# ADCduinoModule_Sensor_1.net
KiCad netlist of a schematic drawn in Altium Designer
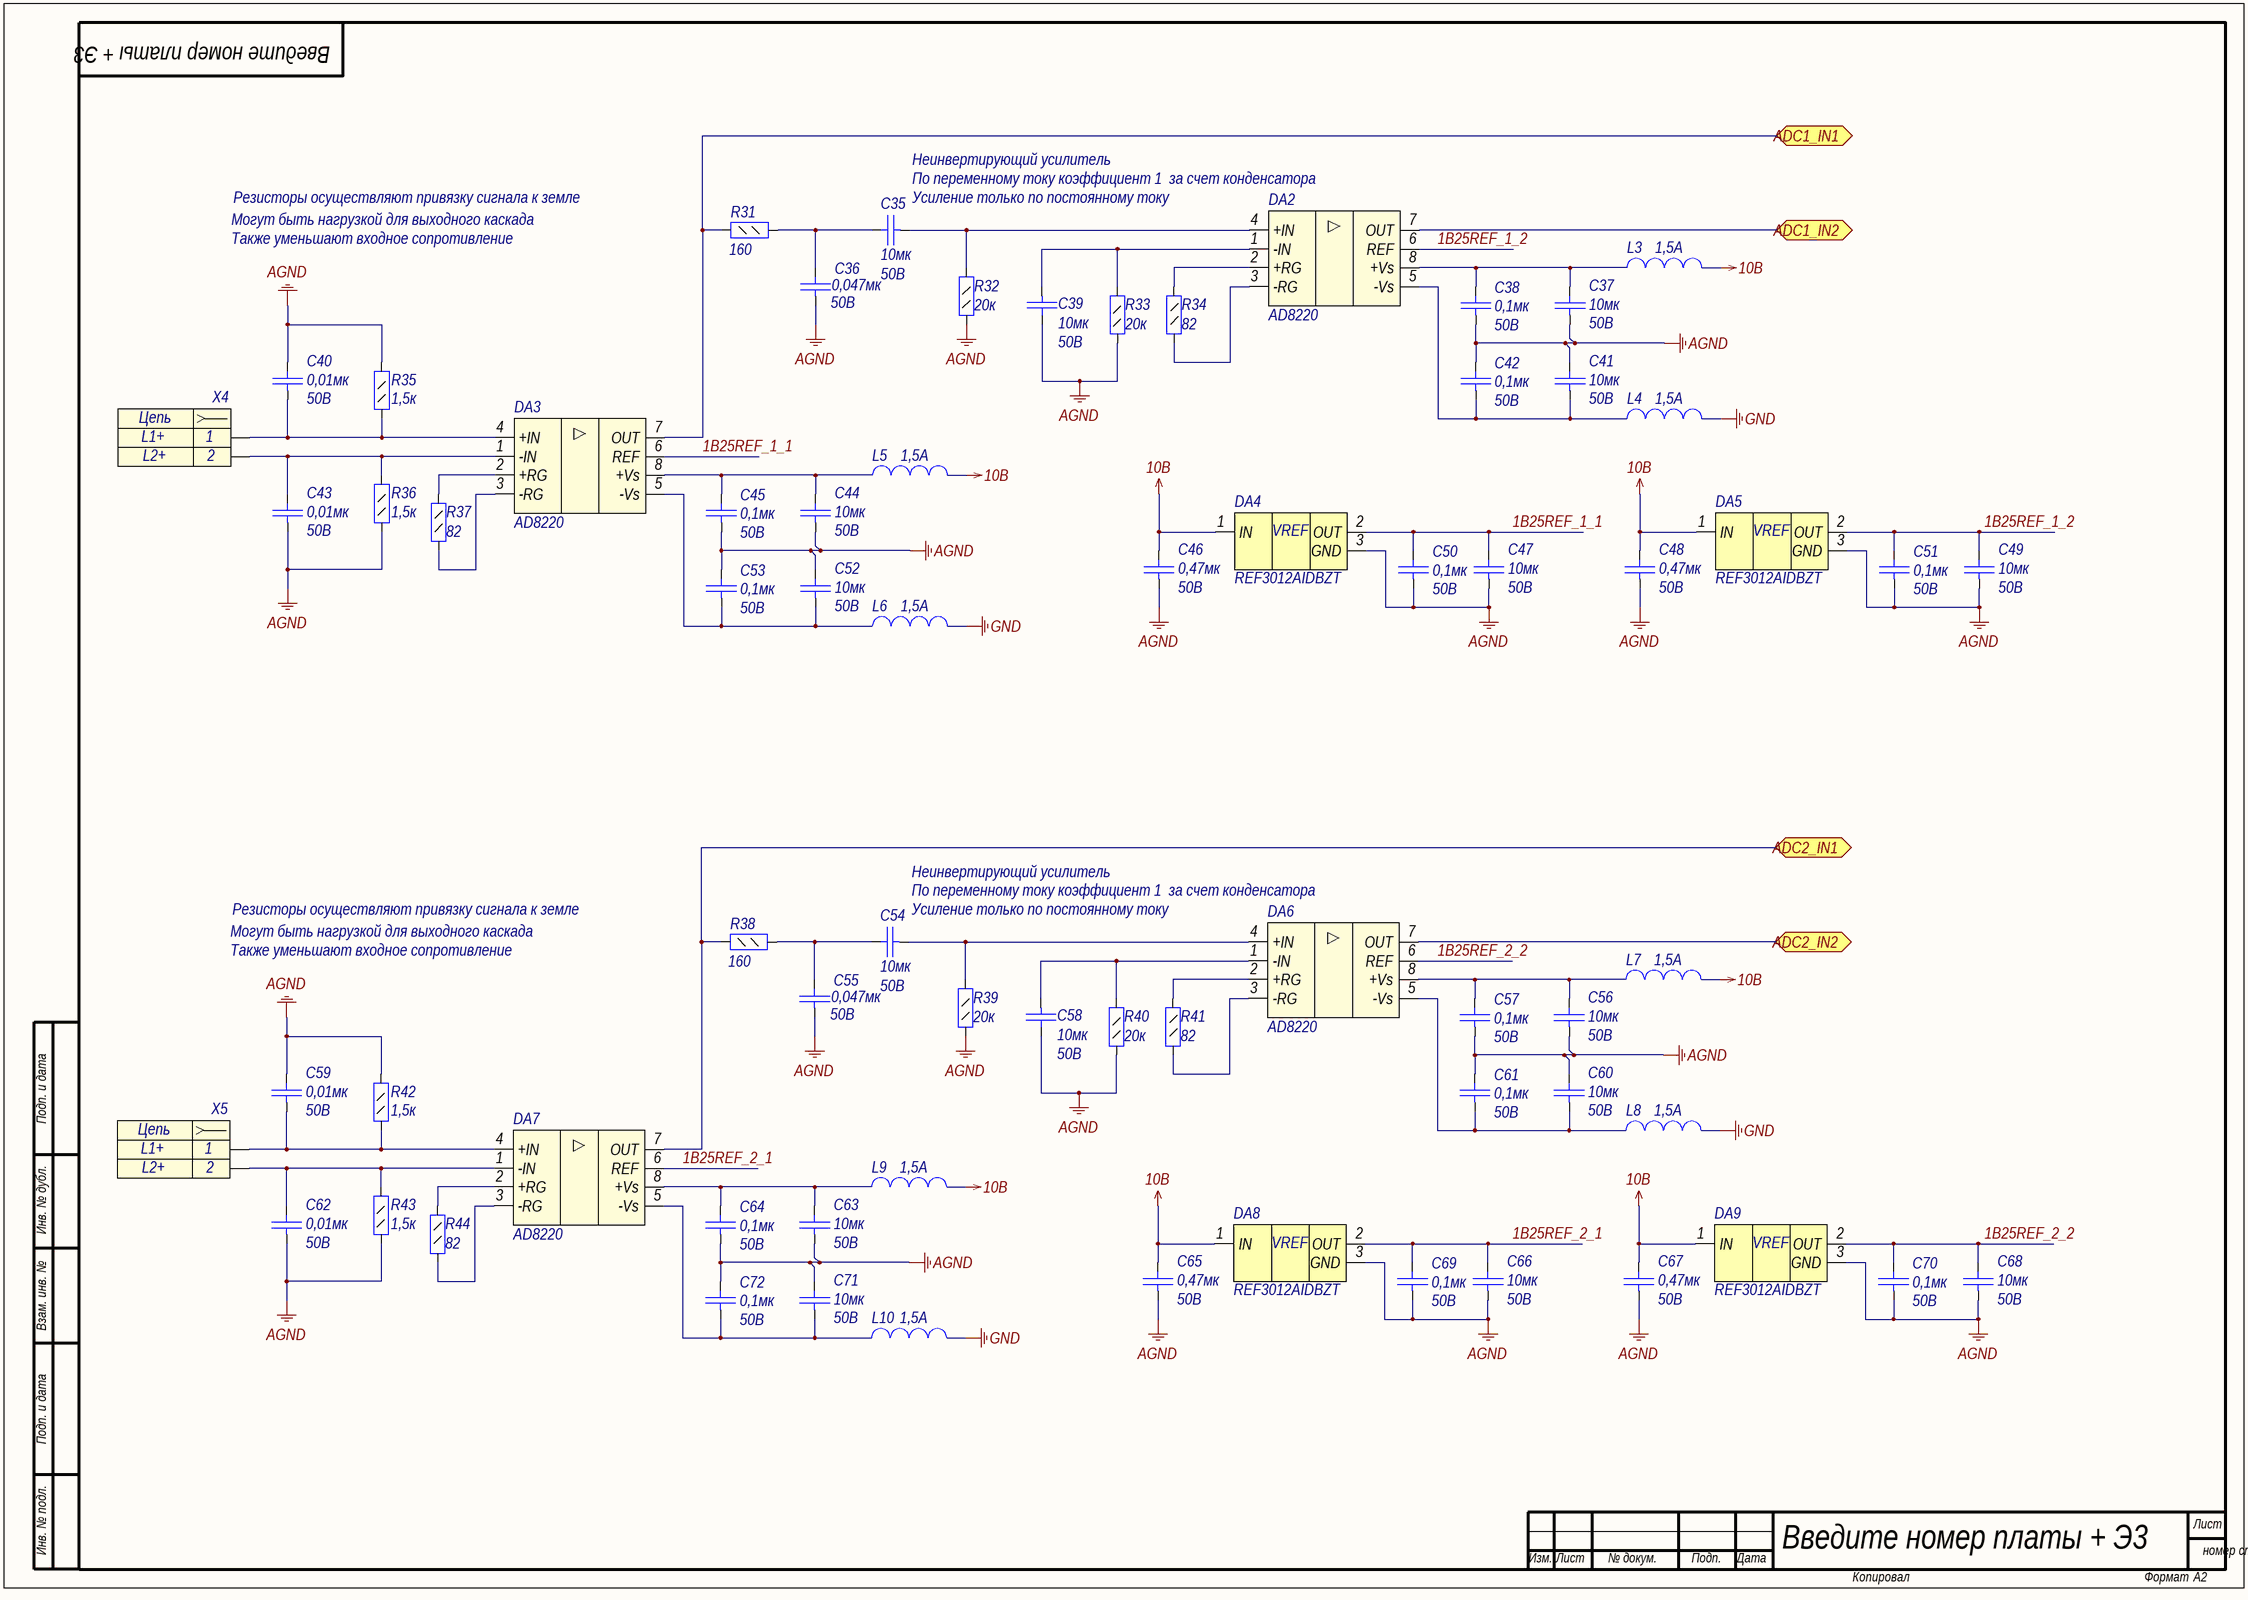
[diagram p0: ADCduinoModule_Sensor_1.SchDoc]

(export (version "E")
  (design (tool "Eeschema 10.0.6"))
  (components
    (comp (ref "C35")
      (value "10мк")
      (footprint "C1210")
      (description "Конденсатор")
      (fields
        (field (name "VOLTAGE") "50В")
        (field (name "PART NUMBER") "GRM32ER71H106K")
        (field (name "Comment") "Capacitor")
      )
      (libsource (lib "MOP44") (part "Capacitor"))
    )
    (comp (ref "C36")
      (value "0,047мк")
      (footprint "C0805")
      (description "Конденсатор")
      (fields
        (field (name "VOLTAGE") "50B")
        (field (name "PART NUMBER") "GRM21BR71H473K")
        (field (name "Comment") "Capacitor")
      )
      (libsource (lib "MOP44") (part "Capacitor"))
    )
    (comp (ref "C37")
      (value "10мк")
      (footprint "C1210")
      (description "Конденсатор")
      (fields
        (field (name "VOLTAGE") "50В")
        (field (name "PART NUMBER") "GRM32ER71H106K")
        (field (name "Comment") "Capacitor")
      )
      (libsource (lib "MOP44") (part "Capacitor"))
    )
    (comp (ref "C38")
      (value "0,1мк")
      (footprint "C0805")
      (description "Конденсатор")
      (fields
        (field (name "VOLTAGE") "50B")
        (field (name "PART NUMBER") "GRM21BR71H104K**")
        (field (name "Comment") "Capacitor")
      )
      (libsource (lib "MOP44") (part "Capacitor"))
    )
    (comp (ref "C39")
      (value "10мк")
      (footprint "C1210")
      (description "Конденсатор")
      (fields
        (field (name "VOLTAGE") "50В")
        (field (name "PART NUMBER") "GRM32ER71H106K")
        (field (name "Comment") "Capacitor")
      )
      (libsource (lib "MOP44") (part "Capacitor"))
    )
    (comp (ref "C40")
      (value "0,01мк")
      (footprint "C0805")
      (description "Конденсатор")
      (fields
        (field (name "VOLTAGE") "50B")
        (field (name "PART NUMBER") "GRM216R71H103K")
        (field (name "Comment") "Capacitor")
      )
      (libsource (lib "MOP44") (part "Capacitor"))
    )
    (comp (ref "C41")
      (value "10мк")
      (footprint "C1210")
      (description "Конденсатор")
      (fields
        (field (name "VOLTAGE") "50В")
        (field (name "PART NUMBER") "GRM32ER71H106K")
        (field (name "Comment") "Capacitor")
      )
      (libsource (lib "MOP44") (part "Capacitor"))
    )
    (comp (ref "C42")
      (value "0,1мк")
      (footprint "C0805")
      (description "Конденсатор")
      (fields
        (field (name "VOLTAGE") "50B")
        (field (name "PART NUMBER") "GRM21BR71H104K**")
        (field (name "Comment") "Capacitor")
      )
      (libsource (lib "MOP44") (part "Capacitor"))
    )
    (comp (ref "C43")
      (value "0,01мк")
      (footprint "C0805")
      (description "Конденсатор")
      (fields
        (field (name "VOLTAGE") "50B")
        (field (name "PART NUMBER") "GRM216R71H103K")
        (field (name "Comment") "Capacitor")
      )
      (libsource (lib "MOP44") (part "Capacitor"))
    )
    (comp (ref "C44")
      (value "10мк")
      (footprint "C1210")
      (description "Конденсатор")
      (fields
        (field (name "VOLTAGE") "50В")
        (field (name "PART NUMBER") "GRM32ER71H106K")
        (field (name "Comment") "Capacitor")
      )
      (libsource (lib "MOP44") (part "Capacitor"))
    )
    (comp (ref "C45")
      (value "0,1мк")
      (footprint "C0805")
      (description "Конденсатор")
      (fields
        (field (name "VOLTAGE") "50B")
        (field (name "PART NUMBER") "GRM21BR71H104K**")
        (field (name "Comment") "Capacitor")
      )
      (libsource (lib "MOP44") (part "Capacitor"))
    )
    (comp (ref "C46")
      (value "0,47мк")
      (footprint "C0805")
      (description "Конденсатор")
      (fields
        (field (name "VOLTAGE") "50B")
        (field (name "PART NUMBER") "GRM219R71C474K")
        (field (name "Comment") "Capacitor")
      )
      (libsource (lib "MOP44") (part "Capacitor"))
    )
    (comp (ref "C47")
      (value "10мк")
      (footprint "C1210")
      (description "Конденсатор")
      (fields
        (field (name "VOLTAGE") "50В")
        (field (name "PART NUMBER") "GRM32ER71H106K")
        (field (name "Comment") "Capacitor")
      )
      (libsource (lib "MOP44") (part "Capacitor"))
    )
    (comp (ref "C48")
      (value "0,47мк")
      (footprint "C0805")
      (description "Конденсатор")
      (fields
        (field (name "VOLTAGE") "50B")
        (field (name "PART NUMBER") "GRM219R71C474K")
        (field (name "Comment") "Capacitor")
      )
      (libsource (lib "MOP44") (part "Capacitor"))
    )
    (comp (ref "C49")
      (value "10мк")
      (footprint "C1210")
      (description "Конденсатор")
      (fields
        (field (name "VOLTAGE") "50В")
        (field (name "PART NUMBER") "GRM32ER71H106K")
        (field (name "Comment") "Capacitor")
      )
      (libsource (lib "MOP44") (part "Capacitor"))
    )
    (comp (ref "C50")
      (value "0,1мк")
      (footprint "C0805")
      (description "Конденсатор")
      (fields
        (field (name "VOLTAGE") "50B")
        (field (name "PART NUMBER") "GRM21BR71H104K**")
        (field (name "Comment") "Capacitor")
      )
      (libsource (lib "MOP44") (part "Capacitor"))
    )
    (comp (ref "C51")
      (value "0,1мк")
      (footprint "C0805")
      (description "Конденсатор")
      (fields
        (field (name "VOLTAGE") "50B")
        (field (name "PART NUMBER") "GRM21BR71H104K**")
        (field (name "Comment") "Capacitor")
      )
      (libsource (lib "MOP44") (part "Capacitor"))
    )
    (comp (ref "C52")
      (value "10мк")
      (footprint "C1210")
      (description "Конденсатор")
      (fields
        (field (name "VOLTAGE") "50В")
        (field (name "PART NUMBER") "GRM32ER71H106K")
        (field (name "Comment") "Capacitor")
      )
      (libsource (lib "MOP44") (part "Capacitor"))
    )
    (comp (ref "C53")
      (value "0,1мк")
      (footprint "C0805")
      (description "Конденсатор")
      (fields
        (field (name "VOLTAGE") "50B")
        (field (name "PART NUMBER") "GRM21BR71H104K**")
        (field (name "Comment") "Capacitor")
      )
      (libsource (lib "MOP44") (part "Capacitor"))
    )
    (comp (ref "C54")
      (value "10мк")
      (footprint "C1210")
      (description "Конденсатор")
      (fields
        (field (name "VOLTAGE") "50В")
        (field (name "PART NUMBER") "GRM32ER71H106K")
        (field (name "Comment") "Capacitor")
      )
      (libsource (lib "MOP44") (part "Capacitor"))
    )
    (comp (ref "C55")
      (value "0,047мк")
      (footprint "C0805")
      (description "Конденсатор")
      (fields
        (field (name "VOLTAGE") "50B")
        (field (name "PART NUMBER") "GRM21BR71H473K")
        (field (name "Comment") "Capacitor")
      )
      (libsource (lib "MOP44") (part "Capacitor"))
    )
    (comp (ref "C56")
      (value "10мк")
      (footprint "C1210")
      (description "Конденсатор")
      (fields
        (field (name "VOLTAGE") "50В")
        (field (name "PART NUMBER") "GRM32ER71H106K")
        (field (name "Comment") "Capacitor")
      )
      (libsource (lib "MOP44") (part "Capacitor"))
    )
    (comp (ref "C57")
      (value "0,1мк")
      (footprint "C0805")
      (description "Конденсатор")
      (fields
        (field (name "VOLTAGE") "50B")
        (field (name "PART NUMBER") "GRM21BR71H104K**")
        (field (name "Comment") "Capacitor")
      )
      (libsource (lib "MOP44") (part "Capacitor"))
    )
    (comp (ref "C58")
      (value "10мк")
      (footprint "C1210")
      (description "Конденсатор")
      (fields
        (field (name "VOLTAGE") "50В")
        (field (name "PART NUMBER") "GRM32ER71H106K")
        (field (name "Comment") "Capacitor")
      )
      (libsource (lib "MOP44") (part "Capacitor"))
    )
    (comp (ref "C59")
      (value "0,01мк")
      (footprint "C0805")
      (description "Конденсатор")
      (fields
        (field (name "VOLTAGE") "50B")
        (field (name "PART NUMBER") "GRM216R71H103K")
        (field (name "Comment") "Capacitor")
      )
      (libsource (lib "MOP44") (part "Capacitor"))
    )
    (comp (ref "C60")
      (value "10мк")
      (footprint "C1210")
      (description "Конденсатор")
      (fields
        (field (name "VOLTAGE") "50В")
        (field (name "PART NUMBER") "GRM32ER71H106K")
        (field (name "Comment") "Capacitor")
      )
      (libsource (lib "MOP44") (part "Capacitor"))
    )
    (comp (ref "C61")
      (value "0,1мк")
      (footprint "C0805")
      (description "Конденсатор")
      (fields
        (field (name "VOLTAGE") "50B")
        (field (name "PART NUMBER") "GRM21BR71H104K**")
        (field (name "Comment") "Capacitor")
      )
      (libsource (lib "MOP44") (part "Capacitor"))
    )
    (comp (ref "C62")
      (value "0,01мк")
      (footprint "C0805")
      (description "Конденсатор")
      (fields
        (field (name "VOLTAGE") "50B")
        (field (name "PART NUMBER") "GRM216R71H103K")
        (field (name "Comment") "Capacitor")
      )
      (libsource (lib "MOP44") (part "Capacitor"))
    )
    (comp (ref "C63")
      (value "10мк")
      (footprint "C1210")
      (description "Конденсатор")
      (fields
        (field (name "VOLTAGE") "50В")
        (field (name "PART NUMBER") "GRM32ER71H106K")
        (field (name "Comment") "Capacitor")
      )
      (libsource (lib "MOP44") (part "Capacitor"))
    )
    (comp (ref "C64")
      (value "0,1мк")
      (footprint "C0805")
      (description "Конденсатор")
      (fields
        (field (name "VOLTAGE") "50B")
        (field (name "PART NUMBER") "GRM21BR71H104K**")
        (field (name "Comment") "Capacitor")
      )
      (libsource (lib "MOP44") (part "Capacitor"))
    )
    (comp (ref "C65")
      (value "0,47мк")
      (footprint "C0805")
      (description "Конденсатор")
      (fields
        (field (name "VOLTAGE") "50B")
        (field (name "PART NUMBER") "GRM219R71C474K")
        (field (name "Comment") "Capacitor")
      )
      (libsource (lib "MOP44") (part "Capacitor"))
    )
    (comp (ref "C66")
      (value "10мк")
      (footprint "C1210")
      (description "Конденсатор")
      (fields
        (field (name "VOLTAGE") "50В")
        (field (name "PART NUMBER") "GRM32ER71H106K")
        (field (name "Comment") "Capacitor")
      )
      (libsource (lib "MOP44") (part "Capacitor"))
    )
    (comp (ref "C67")
      (value "0,47мк")
      (footprint "C0805")
      (description "Конденсатор")
      (fields
        (field (name "VOLTAGE") "50B")
        (field (name "PART NUMBER") "GRM219R71C474K")
        (field (name "Comment") "Capacitor")
      )
      (libsource (lib "MOP44") (part "Capacitor"))
    )
    (comp (ref "C68")
      (value "10мк")
      (footprint "C1210")
      (description "Конденсатор")
      (fields
        (field (name "VOLTAGE") "50В")
        (field (name "PART NUMBER") "GRM32ER71H106K")
        (field (name "Comment") "Capacitor")
      )
      (libsource (lib "MOP44") (part "Capacitor"))
    )
    (comp (ref "C69")
      (value "0,1мк")
      (footprint "C0805")
      (description "Конденсатор")
      (fields
        (field (name "VOLTAGE") "50B")
        (field (name "PART NUMBER") "GRM21BR71H104K**")
        (field (name "Comment") "Capacitor")
      )
      (libsource (lib "MOP44") (part "Capacitor"))
    )
    (comp (ref "C70")
      (value "0,1мк")
      (footprint "C0805")
      (description "Конденсатор")
      (fields
        (field (name "VOLTAGE") "50B")
        (field (name "PART NUMBER") "GRM21BR71H104K**")
        (field (name "Comment") "Capacitor")
      )
      (libsource (lib "MOP44") (part "Capacitor"))
    )
    (comp (ref "C71")
      (value "10мк")
      (footprint "C1210")
      (description "Конденсатор")
      (fields
        (field (name "VOLTAGE") "50В")
        (field (name "PART NUMBER") "GRM32ER71H106K")
        (field (name "Comment") "Capacitor")
      )
      (libsource (lib "MOP44") (part "Capacitor"))
    )
    (comp (ref "C72")
      (value "0,1мк")
      (footprint "C0805")
      (description "Конденсатор")
      (fields
        (field (name "VOLTAGE") "50B")
        (field (name "PART NUMBER") "GRM21BR71H104K**")
        (field (name "Comment") "Capacitor")
      )
      (libsource (lib "MOP44") (part "Capacitor"))
    )
    (comp (ref "DA2")
      (value "AD8220")
      (footprint "MSOP8")
      (description "JFET Input Instrumentation Amplifier")
      (fields (field (name "PART NUMBER") "AD8220ARMZ"))
      (libsource (lib "MOP44") (part "AD8220"))
    )
    (comp (ref "DA3")
      (value "AD8220")
      (footprint "MSOP8")
      (description "JFET Input Instrumentation Amplifier")
      (fields (field (name "PART NUMBER") "AD8220ARMZ"))
      (libsource (lib "MOP44") (part "AD8220"))
    )
    (comp (ref "DA4")
      (value "REF30xx")
      (footprint "SOT23-3")
      (description "CMOS Voltage Reference")
      (fields (field (name "PART NUMBER") "REF3012AIDBZT") (field (name "MANUFACTURER") "Texas Instruments"))
      (libsource (lib "MOP44") (part "REF30xx"))
    )
    (comp (ref "DA5")
      (value "REF30xx")
      (footprint "SOT23-3")
      (description "CMOS Voltage Reference")
      (fields (field (name "PART NUMBER") "REF3012AIDBZT") (field (name "MANUFACTURER") "Texas Instruments"))
      (libsource (lib "MOP44") (part "REF30xx"))
    )
    (comp (ref "DA6")
      (value "AD8220")
      (footprint "MSOP8")
      (description "JFET Input Instrumentation Amplifier")
      (fields (field (name "PART NUMBER") "AD8220ARMZ"))
      (libsource (lib "") (part "AD8220_1"))
    )
    (comp (ref "DA7")
      (value "AD8220")
      (footprint "MSOP8")
      (description "JFET Input Instrumentation Amplifier")
      (fields (field (name "PART NUMBER") "AD8220ARMZ"))
      (libsource (lib "") (part "AD8220_1"))
    )
    (comp (ref "DA8")
      (value "REF30xx")
      (footprint "SOT23-3")
      (description "CMOS Voltage Reference")
      (fields (field (name "PART NUMBER") "REF3012AIDBZT") (field (name "MANUFACTURER") "Texas Instruments"))
      (libsource (lib "MOP44") (part "REF30xx"))
    )
    (comp (ref "DA9")
      (value "REF30xx")
      (footprint "SOT23-3")
      (description "CMOS Voltage Reference")
      (fields (field (name "PART NUMBER") "REF3012AIDBZT") (field (name "MANUFACTURER") "Texas Instruments"))
      (libsource (lib "MOP44") (part "REF30xx"))
    )
    (comp (ref "L3")
      (value "Inductor")
      (footprint "L0603")
      (description "EMI Suppression Filter")
      (fields (field (name "RATED CURRENT") "1,5A") (field (name "PART NUMBER") "BLM18PG181SN1D"))
      (libsource (lib "MOP44") (part "Inductor"))
    )
    (comp (ref "L4")
      (value "Inductor")
      (footprint "L0603")
      (description "EMI Suppression Filter")
      (fields (field (name "RATED CURRENT") "1,5A") (field (name "PART NUMBER") "BLM18PG181SN1D"))
      (libsource (lib "MOP44") (part "Inductor"))
    )
    (comp (ref "L5")
      (value "Inductor")
      (footprint "L0603")
      (description "EMI Suppression Filter")
      (fields (field (name "RATED CURRENT") "1,5A") (field (name "PART NUMBER") "BLM18PG181SN1D"))
      (libsource (lib "MOP44") (part "Inductor"))
    )
    (comp (ref "L6")
      (value "Inductor")
      (footprint "L0603")
      (description "EMI Suppression Filter")
      (fields (field (name "RATED CURRENT") "1,5A") (field (name "PART NUMBER") "BLM18PG181SN1D"))
      (libsource (lib "MOP44") (part "Inductor"))
    )
    (comp (ref "L7")
      (value "Inductor")
      (footprint "L0603")
      (description "EMI Suppression Filter")
      (fields (field (name "RATED CURRENT") "1,5A") (field (name "PART NUMBER") "BLM18PG181SN1D"))
      (libsource (lib "MOP44") (part "Inductor"))
    )
    (comp (ref "L8")
      (value "Inductor")
      (footprint "L0603")
      (description "EMI Suppression Filter")
      (fields (field (name "RATED CURRENT") "1,5A") (field (name "PART NUMBER") "BLM18PG181SN1D"))
      (libsource (lib "MOP44") (part "Inductor"))
    )
    (comp (ref "L9")
      (value "Inductor")
      (footprint "L0603")
      (description "EMI Suppression Filter")
      (fields (field (name "RATED CURRENT") "1,5A") (field (name "PART NUMBER") "BLM18PG181SN1D"))
      (libsource (lib "MOP44") (part "Inductor"))
    )
    (comp (ref "L10")
      (value "Inductor")
      (footprint "L0603")
      (description "EMI Suppression Filter")
      (fields (field (name "RATED CURRENT") "1,5A") (field (name "PART NUMBER") "BLM18PG181SN1D"))
      (libsource (lib "MOP44") (part "Inductor"))
    )
    (comp (ref "R31")
      (value "160")
      (footprint "R0805")
      (description "Резистор")
      (fields (field (name "PART NUMBER") "RC0805FR-07160RL") (field (name "POWER") "0,125Вт"))
      (libsource (lib "") (part "Resistor_0,125Вт_2"))
    )
    (comp (ref "R32")
      (value "20к")
      (footprint "R0805")
      (description "Резистор")
      (fields (field (name "PART NUMBER") "RC0805FR-0720KL") (field (name "POWER") "0,125Вт"))
      (libsource (lib "") (part "Resistor_0,125Вт_1"))
    )
    (comp (ref "R33")
      (value "20к")
      (footprint "R0805")
      (description "Резистор")
      (fields (field (name "PART NUMBER") "RC0805FR-0720KL") (field (name "POWER") "0,125Вт"))
      (libsource (lib "") (part "Resistor_0,125Вт_1"))
    )
    (comp (ref "R34")
      (value "82")
      (footprint "R0805")
      (description "Резистор")
      (fields (field (name "PART NUMBER") "RC0805FR-0782RL") (field (name "POWER") "0,125Вт"))
      (libsource (lib "MOP44") (part "Resistor_0,125Вт"))
    )
    (comp (ref "R35")
      (value "1,5к")
      (footprint "R0805")
      (description "Резистор")
      (fields (field (name "PART NUMBER") "RC0805FR-071K5") (field (name "POWER") "0,125Вт"))
      (libsource (lib "") (part "Resistor_0,125Вт_1"))
    )
    (comp (ref "R36")
      (value "1,5к")
      (footprint "R0805")
      (description "Резистор")
      (fields (field (name "PART NUMBER") "RC0805FR-071K5") (field (name "POWER") "0,125Вт"))
      (libsource (lib "") (part "Resistor_0,125Вт_1"))
    )
    (comp (ref "R37")
      (value "82")
      (footprint "R0805")
      (description "Резистор")
      (fields (field (name "PART NUMBER") "RC0805FR-0782RL") (field (name "POWER") "0,125Вт"))
      (libsource (lib "MOP44") (part "Resistor_0,125Вт"))
    )
    (comp (ref "R38")
      (value "160")
      (footprint "R0805")
      (description "Резистор")
      (fields (field (name "PART NUMBER") "RC0805FR-07160RL") (field (name "POWER") "0,125Вт"))
      (libsource (lib "") (part "Resistor_0,125Вт_2"))
    )
    (comp (ref "R39")
      (value "20к")
      (footprint "R0805")
      (description "Резистор")
      (fields (field (name "PART NUMBER") "RC0805FR-0720KL") (field (name "POWER") "0,125Вт"))
      (libsource (lib "") (part "Resistor_0,125Вт_1"))
    )
    (comp (ref "R40")
      (value "20к")
      (footprint "R0805")
      (description "Резистор")
      (fields (field (name "PART NUMBER") "RC0805FR-0720KL") (field (name "POWER") "0,125Вт"))
      (libsource (lib "") (part "Resistor_0,125Вт_1"))
    )
    (comp (ref "R41")
      (value "82")
      (footprint "R0805")
      (description "Резистор")
      (fields (field (name "PART NUMBER") "RC0805FR-0782RL") (field (name "POWER") "0,125Вт"))
      (libsource (lib "MOP44") (part "Resistor_0,125Вт"))
    )
    (comp (ref "R42")
      (value "1,5к")
      (footprint "R0805")
      (description "Резистор")
      (fields (field (name "PART NUMBER") "RC0805FR-071K5") (field (name "POWER") "0,125Вт"))
      (libsource (lib "") (part "Resistor_0,125Вт_1"))
    )
    (comp (ref "R43")
      (value "1,5к")
      (footprint "R0805")
      (description "Резистор")
      (fields (field (name "PART NUMBER") "RC0805FR-071K5") (field (name "POWER") "0,125Вт"))
      (libsource (lib "") (part "Resistor_0,125Вт_1"))
    )
    (comp (ref "R44")
      (value "82")
      (footprint "R0805")
      (description "Резистор")
      (fields (field (name "PART NUMBER") "RC0805FR-0782RL") (field (name "POWER") "0,125Вт"))
      (libsource (lib "MOP44") (part "Resistor_0,125Вт"))
    )
    (comp (ref "X4")
      (value "Header_2_sct")
      (footprint "TAB_2PAD")
      (description "Разъем - 2 конт. розетка")
      (libsource (lib "") (part "Header_2_sct_1"))
    )
    (comp (ref "X5")
      (value "Header_2_sct")
      (footprint "TAB_2PAD")
      (description "Разъем - 2 конт. розетка")
      (libsource (lib "MOP44") (part "Header_2_sct"))
    )
  )
  (nets
    (net (code "1") (name "/1B25REF_1_1") (class "Default")
      (node (ref "C47") (pin "2") (pinfunction "2_2") (pintype "passive"))
      (node (ref "C50") (pin "2") (pinfunction "2_2") (pintype "passive"))
      (node (ref "DA3") (pin "6") (pinfunction "REF_6") (pintype "passive"))
      (node (ref "DA4") (pin "2") (pinfunction "OUT_2") (pintype "passive"))
    )
    (net (code "2") (name "/1B25REF_1_2") (class "Default")
      (node (ref "C49") (pin "2") (pinfunction "2_2") (pintype "passive"))
      (node (ref "C51") (pin "2") (pinfunction "2_2") (pintype "passive"))
      (node (ref "DA2") (pin "6") (pinfunction "REF_6") (pintype "passive"))
      (node (ref "DA5") (pin "2") (pinfunction "OUT_2") (pintype "passive"))
    )
    (net (code "3") (name "/1B25REF_2_1") (class "Default")
      (node (ref "C66") (pin "2") (pinfunction "2_2") (pintype "passive"))
      (node (ref "C69") (pin "2") (pinfunction "2_2") (pintype "passive"))
      (node (ref "DA7") (pin "6") (pinfunction "REF_6") (pintype "passive"))
      (node (ref "DA8") (pin "2") (pinfunction "OUT_2") (pintype "passive"))
    )
    (net (code "4") (name "/1B25REF_2_2") (class "Default")
      (node (ref "C68") (pin "2") (pinfunction "2_2") (pintype "passive"))
      (node (ref "C70") (pin "2") (pinfunction "2_2") (pintype "passive"))
      (node (ref "DA6") (pin "6") (pinfunction "REF_6") (pintype "passive"))
      (node (ref "DA9") (pin "2") (pinfunction "OUT_2") (pintype "passive"))
    )
    (net (code "5") (name "/ADC1_IN1") (class "Default")
      (node (ref "DA3") (pin "7") (pinfunction "OUT_7") (pintype "passive"))
      (node (ref "R31") (pin "1") (pinfunction "1_1") (pintype "passive"))
    )
    (net (code "6") (name "/ADC1_IN2") (class "Default")
      (node (ref "DA2") (pin "7") (pinfunction "OUT_7") (pintype "passive"))
    )
    (net (code "7") (name "/ADC2_IN1") (class "Default")
      (node (ref "DA7") (pin "7") (pinfunction "OUT_7") (pintype "passive"))
      (node (ref "R38") (pin "1") (pinfunction "1_1") (pintype "passive"))
    )
    (net (code "8") (name "/ADC2_IN2") (class "Default")
      (node (ref "DA6") (pin "7") (pinfunction "OUT_7") (pintype "passive"))
    )
    (net (code "9") (name "10B") (class "Default")
      (node (ref "C46") (pin "2") (pinfunction "2_2") (pintype "passive"))
      (node (ref "C48") (pin "2") (pinfunction "2_2") (pintype "passive"))
      (node (ref "C65") (pin "2") (pinfunction "2_2") (pintype "passive"))
      (node (ref "C67") (pin "2") (pinfunction "2_2") (pintype "passive"))
      (node (ref "DA4") (pin "1") (pinfunction "IN_1") (pintype "passive"))
      (node (ref "DA5") (pin "1") (pinfunction "IN_1") (pintype "passive"))
      (node (ref "DA8") (pin "1") (pinfunction "IN_1") (pintype "passive"))
      (node (ref "DA9") (pin "1") (pinfunction "IN_1") (pintype "passive"))
      (node (ref "L3") (pin "2") (pinfunction "2_2") (pintype "passive"))
      (node (ref "L5") (pin "2") (pinfunction "2_2") (pintype "passive"))
      (node (ref "L7") (pin "2") (pinfunction "2_2") (pintype "passive"))
      (node (ref "L9") (pin "2") (pinfunction "2_2") (pintype "passive"))
    )
    (net (code "10") (name "AGND") (class "Default")
      (node (ref "C36") (pin "1") (pinfunction "1_1") (pintype "passive"))
      (node (ref "C37") (pin "1") (pinfunction "1_1") (pintype "passive"))
      (node (ref "C38") (pin "1") (pinfunction "1_1") (pintype "passive"))
      (node (ref "C39") (pin "2") (pinfunction "2_2") (pintype "passive"))
      (node (ref "C40") (pin "2") (pinfunction "2_2") (pintype "passive"))
      (node (ref "C41") (pin "2") (pinfunction "2_2") (pintype "passive"))
      (node (ref "C42") (pin "2") (pinfunction "2_2") (pintype "passive"))
      (node (ref "C43") (pin "1") (pinfunction "1_1") (pintype "passive"))
      (node (ref "C44") (pin "1") (pinfunction "1_1") (pintype "passive"))
      (node (ref "C45") (pin "1") (pinfunction "1_1") (pintype "passive"))
      (node (ref "C46") (pin "1") (pinfunction "1_1") (pintype "passive"))
      (node (ref "C47") (pin "1") (pinfunction "1_1") (pintype "passive"))
      (node (ref "C48") (pin "1") (pinfunction "1_1") (pintype "passive"))
      (node (ref "C49") (pin "1") (pinfunction "1_1") (pintype "passive"))
      (node (ref "C50") (pin "1") (pinfunction "1_1") (pintype "passive"))
      (node (ref "C51") (pin "1") (pinfunction "1_1") (pintype "passive"))
      (node (ref "C52") (pin "2") (pinfunction "2_2") (pintype "passive"))
      (node (ref "C53") (pin "2") (pinfunction "2_2") (pintype "passive"))
      (node (ref "C55") (pin "1") (pinfunction "1_1") (pintype "passive"))
      (node (ref "C56") (pin "1") (pinfunction "1_1") (pintype "passive"))
      (node (ref "C57") (pin "1") (pinfunction "1_1") (pintype "passive"))
      (node (ref "C58") (pin "2") (pinfunction "2_2") (pintype "passive"))
      (node (ref "C59") (pin "2") (pinfunction "2_2") (pintype "passive"))
      (node (ref "C60") (pin "2") (pinfunction "2_2") (pintype "passive"))
      (node (ref "C61") (pin "2") (pinfunction "2_2") (pintype "passive"))
      (node (ref "C62") (pin "1") (pinfunction "1_1") (pintype "passive"))
      (node (ref "C63") (pin "1") (pinfunction "1_1") (pintype "passive"))
      (node (ref "C64") (pin "1") (pinfunction "1_1") (pintype "passive"))
      (node (ref "C65") (pin "1") (pinfunction "1_1") (pintype "passive"))
      (node (ref "C66") (pin "1") (pinfunction "1_1") (pintype "passive"))
      (node (ref "C67") (pin "1") (pinfunction "1_1") (pintype "passive"))
      (node (ref "C68") (pin "1") (pinfunction "1_1") (pintype "passive"))
      (node (ref "C69") (pin "1") (pinfunction "1_1") (pintype "passive"))
      (node (ref "C70") (pin "1") (pinfunction "1_1") (pintype "passive"))
      (node (ref "C71") (pin "2") (pinfunction "2_2") (pintype "passive"))
      (node (ref "C72") (pin "2") (pinfunction "2_2") (pintype "passive"))
      (node (ref "DA4") (pin "3") (pinfunction "GND_3") (pintype "passive"))
      (node (ref "DA5") (pin "3") (pinfunction "GND_3") (pintype "passive"))
      (node (ref "DA8") (pin "3") (pinfunction "GND_3") (pintype "passive"))
      (node (ref "DA9") (pin "3") (pinfunction "GND_3") (pintype "passive"))
      (node (ref "R32") (pin "1") (pinfunction "1_1") (pintype "passive"))
      (node (ref "R33") (pin "1") (pinfunction "1_1") (pintype "passive"))
      (node (ref "R35") (pin "2") (pinfunction "2_2") (pintype "passive"))
      (node (ref "R36") (pin "1") (pinfunction "1_1") (pintype "passive"))
      (node (ref "R39") (pin "1") (pinfunction "1_1") (pintype "passive"))
      (node (ref "R40") (pin "1") (pinfunction "1_1") (pintype "passive"))
      (node (ref "R42") (pin "2") (pinfunction "2_2") (pintype "passive"))
      (node (ref "R43") (pin "1") (pinfunction "1_1") (pintype "passive"))
    )
    (net (code "11") (name "GND") (class "Default")
      (node (ref "L10") (pin "2") (pinfunction "2_2") (pintype "passive"))
      (node (ref "L4") (pin "2") (pinfunction "2_2") (pintype "passive"))
      (node (ref "L6") (pin "2") (pinfunction "2_2") (pintype "passive"))
      (node (ref "L8") (pin "2") (pinfunction "2_2") (pintype "passive"))
    )
    (net (code "12") (name "Net-(C35-Pad2)") (class "Default")
      (node (ref "C35") (pin "2") (pinfunction "2_2") (pintype "passive"))
      (node (ref "C36") (pin "2") (pinfunction "2_2") (pintype "passive"))
      (node (ref "R31") (pin "2") (pinfunction "2_2") (pintype "passive"))
    )
    (net (code "13") (name "Net-(C54-Pad2)") (class "Default")
      (node (ref "C54") (pin "2") (pinfunction "2_2") (pintype "passive"))
      (node (ref "C55") (pin "2") (pinfunction "2_2") (pintype "passive"))
      (node (ref "R38") (pin "2") (pinfunction "2_2") (pintype "passive"))
    )
    (net (code "14") (name "Net-(DA2-+IN)") (class "Default")
      (node (ref "C35") (pin "1") (pinfunction "1_1") (pintype "passive"))
      (node (ref "DA2") (pin "4") (pinfunction "+IN_4") (pintype "passive"))
      (node (ref "R32") (pin "2") (pinfunction "2_2") (pintype "passive"))
    )
    (net (code "15") (name "Net-(DA2-+RG)") (class "Default")
      (node (ref "DA2") (pin "2") (pinfunction "+RG_2") (pintype "passive"))
      (node (ref "R34") (pin "1") (pinfunction "1_1") (pintype "passive"))
    )
    (net (code "16") (name "Net-(DA2-+Vs)") (class "Default")
      (node (ref "C37") (pin "2") (pinfunction "2_2") (pintype "passive"))
      (node (ref "C38") (pin "2") (pinfunction "2_2") (pintype "passive"))
      (node (ref "DA2") (pin "8") (pinfunction "+Vs_8") (pintype "passive"))
      (node (ref "L3") (pin "1") (pinfunction "1_1") (pintype "passive"))
    )
    (net (code "17") (name "Net-(DA2--IN)") (class "Default")
      (node (ref "C39") (pin "1") (pinfunction "1_1") (pintype "passive"))
      (node (ref "DA2") (pin "1") (pinfunction "-IN_1") (pintype "passive"))
      (node (ref "R33") (pin "2") (pinfunction "2_2") (pintype "passive"))
    )
    (net (code "18") (name "Net-(DA2--RG)") (class "Default")
      (node (ref "DA2") (pin "3") (pinfunction "-RG_3") (pintype "passive"))
      (node (ref "R34") (pin "2") (pinfunction "2_2") (pintype "passive"))
    )
    (net (code "19") (name "Net-(DA2--Vs)") (class "Default")
      (node (ref "C41") (pin "1") (pinfunction "1_1") (pintype "passive"))
      (node (ref "C42") (pin "1") (pinfunction "1_1") (pintype "passive"))
      (node (ref "DA2") (pin "5") (pinfunction "-Vs_5") (pintype "passive"))
      (node (ref "L4") (pin "1") (pinfunction "1_1") (pintype "passive"))
    )
    (net (code "20") (name "Net-(DA3-+IN)") (class "Default")
      (node (ref "C40") (pin "1") (pinfunction "1_1") (pintype "passive"))
      (node (ref "DA3") (pin "4") (pinfunction "+IN_4") (pintype "passive"))
      (node (ref "R35") (pin "1") (pinfunction "1_1") (pintype "passive"))
      (node (ref "X4") (pin "1") (pinfunction "1_1") (pintype "passive"))
    )
    (net (code "21") (name "Net-(DA3-+RG)") (class "Default")
      (node (ref "DA3") (pin "2") (pinfunction "+RG_2") (pintype "passive"))
      (node (ref "R37") (pin "1") (pinfunction "1_1") (pintype "passive"))
    )
    (net (code "22") (name "Net-(DA3-+Vs)") (class "Default")
      (node (ref "C44") (pin "2") (pinfunction "2_2") (pintype "passive"))
      (node (ref "C45") (pin "2") (pinfunction "2_2") (pintype "passive"))
      (node (ref "DA3") (pin "8") (pinfunction "+Vs_8") (pintype "passive"))
      (node (ref "L5") (pin "1") (pinfunction "1_1") (pintype "passive"))
    )
    (net (code "23") (name "Net-(DA3--IN)") (class "Default")
      (node (ref "C43") (pin "2") (pinfunction "2_2") (pintype "passive"))
      (node (ref "DA3") (pin "1") (pinfunction "-IN_1") (pintype "passive"))
      (node (ref "R36") (pin "2") (pinfunction "2_2") (pintype "passive"))
      (node (ref "X4") (pin "2") (pinfunction "2_2") (pintype "passive"))
    )
    (net (code "24") (name "Net-(DA3--RG)") (class "Default")
      (node (ref "DA3") (pin "3") (pinfunction "-RG_3") (pintype "passive"))
      (node (ref "R37") (pin "2") (pinfunction "2_2") (pintype "passive"))
    )
    (net (code "25") (name "Net-(DA3--Vs)") (class "Default")
      (node (ref "C52") (pin "1") (pinfunction "1_1") (pintype "passive"))
      (node (ref "C53") (pin "1") (pinfunction "1_1") (pintype "passive"))
      (node (ref "DA3") (pin "5") (pinfunction "-Vs_5") (pintype "passive"))
      (node (ref "L6") (pin "1") (pinfunction "1_1") (pintype "passive"))
    )
    (net (code "26") (name "Net-(DA6-+IN)") (class "Default")
      (node (ref "C54") (pin "1") (pinfunction "1_1") (pintype "passive"))
      (node (ref "DA6") (pin "4") (pinfunction "+IN_4") (pintype "passive"))
      (node (ref "R39") (pin "2") (pinfunction "2_2") (pintype "passive"))
    )
    (net (code "27") (name "Net-(DA6-+RG)") (class "Default")
      (node (ref "DA6") (pin "2") (pinfunction "+RG_2") (pintype "passive"))
      (node (ref "R41") (pin "1") (pinfunction "1_1") (pintype "passive"))
    )
    (net (code "28") (name "Net-(DA6-+Vs)") (class "Default")
      (node (ref "C56") (pin "2") (pinfunction "2_2") (pintype "passive"))
      (node (ref "C57") (pin "2") (pinfunction "2_2") (pintype "passive"))
      (node (ref "DA6") (pin "8") (pinfunction "+Vs_8") (pintype "passive"))
      (node (ref "L7") (pin "1") (pinfunction "1_1") (pintype "passive"))
    )
    (net (code "29") (name "Net-(DA6--IN)") (class "Default")
      (node (ref "C58") (pin "1") (pinfunction "1_1") (pintype "passive"))
      (node (ref "DA6") (pin "1") (pinfunction "-IN_1") (pintype "passive"))
      (node (ref "R40") (pin "2") (pinfunction "2_2") (pintype "passive"))
    )
    (net (code "30") (name "Net-(DA6--RG)") (class "Default")
      (node (ref "DA6") (pin "3") (pinfunction "-RG_3") (pintype "passive"))
      (node (ref "R41") (pin "2") (pinfunction "2_2") (pintype "passive"))
    )
    (net (code "31") (name "Net-(DA6--Vs)") (class "Default")
      (node (ref "C60") (pin "1") (pinfunction "1_1") (pintype "passive"))
      (node (ref "C61") (pin "1") (pinfunction "1_1") (pintype "passive"))
      (node (ref "DA6") (pin "5") (pinfunction "-Vs_5") (pintype "passive"))
      (node (ref "L8") (pin "1") (pinfunction "1_1") (pintype "passive"))
    )
    (net (code "32") (name "Net-(DA7-+IN)") (class "Default")
      (node (ref "C59") (pin "1") (pinfunction "1_1") (pintype "passive"))
      (node (ref "DA7") (pin "4") (pinfunction "+IN_4") (pintype "passive"))
      (node (ref "R42") (pin "1") (pinfunction "1_1") (pintype "passive"))
      (node (ref "X5") (pin "1") (pinfunction "1_1") (pintype "passive"))
    )
    (net (code "33") (name "Net-(DA7-+RG)") (class "Default")
      (node (ref "DA7") (pin "2") (pinfunction "+RG_2") (pintype "passive"))
      (node (ref "R44") (pin "1") (pinfunction "1_1") (pintype "passive"))
    )
    (net (code "34") (name "Net-(DA7-+Vs)") (class "Default")
      (node (ref "C63") (pin "2") (pinfunction "2_2") (pintype "passive"))
      (node (ref "C64") (pin "2") (pinfunction "2_2") (pintype "passive"))
      (node (ref "DA7") (pin "8") (pinfunction "+Vs_8") (pintype "passive"))
      (node (ref "L9") (pin "1") (pinfunction "1_1") (pintype "passive"))
    )
    (net (code "35") (name "Net-(DA7--IN)") (class "Default")
      (node (ref "C62") (pin "2") (pinfunction "2_2") (pintype "passive"))
      (node (ref "DA7") (pin "1") (pinfunction "-IN_1") (pintype "passive"))
      (node (ref "R43") (pin "2") (pinfunction "2_2") (pintype "passive"))
      (node (ref "X5") (pin "2") (pinfunction "2_2") (pintype "passive"))
    )
    (net (code "36") (name "Net-(DA7--RG)") (class "Default")
      (node (ref "DA7") (pin "3") (pinfunction "-RG_3") (pintype "passive"))
      (node (ref "R44") (pin "2") (pinfunction "2_2") (pintype "passive"))
    )
    (net (code "37") (name "Net-(DA7--Vs)") (class "Default")
      (node (ref "C71") (pin "1") (pinfunction "1_1") (pintype "passive"))
      (node (ref "C72") (pin "1") (pinfunction "1_1") (pintype "passive"))
      (node (ref "DA7") (pin "5") (pinfunction "-Vs_5") (pintype "passive"))
      (node (ref "L10") (pin "1") (pinfunction "1_1") (pintype "passive"))
    )
  )
)
